# Ex_EEPROM_SOP16.net
KiCad netlist of a schematic drawn in EAGLE
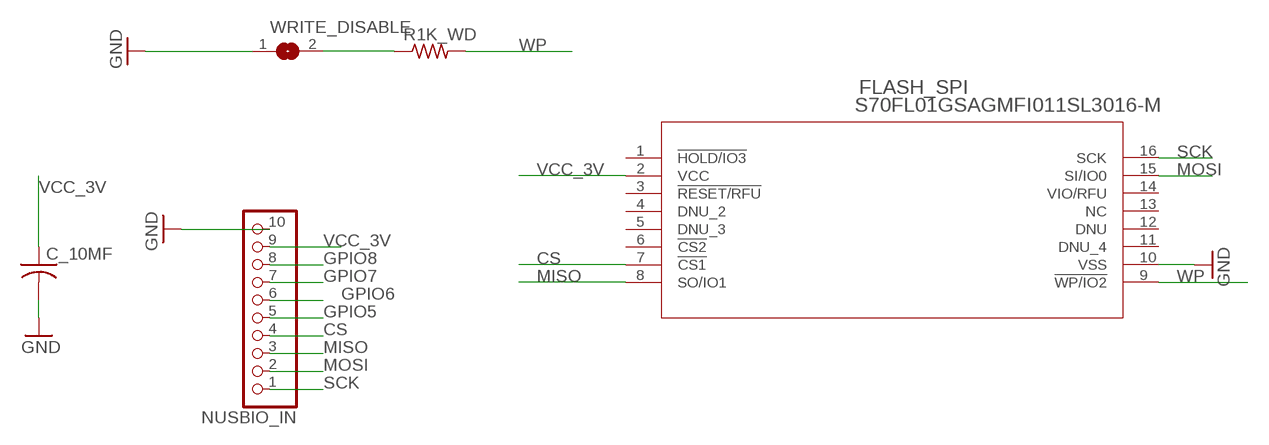
[diagram p0: schematic, sheet 1]

(export (version "E")
  (design (tool "Eeschema 10.0.6"))
  (components
    (comp (ref "C_10MF")
      (value "C-USC1206")
      (footprint "eagle-import:C1206")
      (libsource (lib "eagle-import") (part "C-USC1206"))
    )
    (comp (ref "FLASH_SPI")
      (value "S70FL01GSAGMFI011SL3016-M")
      (footprint "eagle-import:SL3016-M")
      (fields (field (name "MANUFACTURER_PART_NUMBER") "S70FL01GSAGMFI011"))
      (libsource (lib "eagle-import") (part "S70FL01GSAGMFI011SL3016-M"))
    )
    (comp (ref "NUSBIO_IN")
      (value "PINHD-1X10")
      (footprint "eagle-import:1X10-BIG")
      (libsource (lib "eagle-import") (part "PINHD-1X10"))
    )
    (comp (ref "R1K_WD")
      (value "R-US_R1206")
      (footprint "eagle-import:R1206")
      (libsource (lib "eagle-import") (part "R-US_R1206"))
    )
    (comp (ref "WRITE_DISABLE")
      (value "SOLDERJUMPERREFLOW")
      (footprint "eagle-import:SOLDERJUMPER_REFLOW")
      (libsource (lib "eagle-import") (part "SOLDERJUMPERREFLOW"))
    )
  )
  (nets
    (net (code "1") (name "/CS") (class "Default")
      (node (ref "FLASH_SPI") (pin "7") (pinfunction "~{CS1}_7") (pintype "input"))
      (node (ref "NUSBIO_IN") (pin "4") (pinfunction "4_4") (pintype "passive"))
    )
    (net (code "2") (name "/GPIO5") (class "Default")
      (node (ref "NUSBIO_IN") (pin "5") (pinfunction "5_5") (pintype "passive"))
    )
    (net (code "3") (name "/GPIO6") (class "Default")
      (node (ref "NUSBIO_IN") (pin "6") (pinfunction "6_6") (pintype "passive"))
    )
    (net (code "4") (name "/GPIO7") (class "Default")
      (node (ref "NUSBIO_IN") (pin "7") (pinfunction "7_7") (pintype "passive"))
    )
    (net (code "5") (name "/GPIO8") (class "Default")
      (node (ref "NUSBIO_IN") (pin "8") (pinfunction "8_8") (pintype "passive"))
    )
    (net (code "6") (name "/MISO") (class "Default")
      (node (ref "FLASH_SPI") (pin "8") (pinfunction "SO/IO1_8") (pintype "bidirectional"))
      (node (ref "NUSBIO_IN") (pin "3") (pinfunction "3_3") (pintype "passive"))
    )
    (net (code "7") (name "/MOSI") (class "Default")
      (node (ref "FLASH_SPI") (pin "15") (pinfunction "SI/IO0_15") (pintype "bidirectional"))
      (node (ref "NUSBIO_IN") (pin "2") (pinfunction "2_2") (pintype "passive"))
    )
    (net (code "8") (name "/SCK") (class "Default")
      (node (ref "FLASH_SPI") (pin "16") (pinfunction "SCK_16") (pintype "input"))
      (node (ref "NUSBIO_IN") (pin "1") (pinfunction "1_1") (pintype "passive"))
    )
    (net (code "9") (name "/VCC_3V") (class "Default")
      (node (ref "C_10MF") (pin "1") (pinfunction "1_1") (pintype "passive"))
      (node (ref "FLASH_SPI") (pin "2") (pinfunction "VCC_2") (pintype "power_in"))
      (node (ref "NUSBIO_IN") (pin "9") (pinfunction "9_9") (pintype "passive"))
    )
    (net (code "10") (name "/WP") (class "Default")
      (node (ref "FLASH_SPI") (pin "9") (pinfunction "~{WP/IO2}_9") (pintype "bidirectional"))
      (node (ref "R1K_WD") (pin "2") (pinfunction "2_2") (pintype "passive"))
    )
    (net (code "11") (name "GND") (class "Default")
      (node (ref "C_10MF") (pin "2") (pinfunction "2_2") (pintype "passive"))
      (node (ref "FLASH_SPI") (pin "10") (pinfunction "VSS_10") (pintype "power_in"))
      (node (ref "NUSBIO_IN") (pin "10") (pinfunction "10_10") (pintype "passive"))
      (node (ref "WRITE_DISABLE") (pin "1") (pinfunction "1_1") (pintype "passive"))
    )
    (net (code "12") (name "Net-(R1K_WD-Pad1)") (class "Default")
      (node (ref "R1K_WD") (pin "1") (pinfunction "1_1") (pintype "passive"))
      (node (ref "WRITE_DISABLE") (pin "2") (pinfunction "2_2") (pintype "passive"))
    )
    (net (code "13") (name "unconnected-(FLASH_SPI-DNU-Pad12)") (class "Default")
      (node (ref "FLASH_SPI") (pin "12") (pinfunction "DNU_12") (pintype "no_connect"))
    )
    (net (code "14") (name "unconnected-(FLASH_SPI-DNU_2-Pad4)") (class "Default")
      (node (ref "FLASH_SPI") (pin "4") (pinfunction "DNU_2_4") (pintype "no_connect"))
    )
    (net (code "15") (name "unconnected-(FLASH_SPI-DNU_3-Pad5)") (class "Default")
      (node (ref "FLASH_SPI") (pin "5") (pinfunction "DNU_3_5") (pintype "no_connect"))
    )
    (net (code "16") (name "unconnected-(FLASH_SPI-DNU_4-Pad11)") (class "Default")
      (node (ref "FLASH_SPI") (pin "11") (pinfunction "DNU_4_11") (pintype "no_connect"))
    )
    (net (code "17") (name "unconnected-(FLASH_SPI-NC-Pad13)") (class "Default")
      (node (ref "FLASH_SPI") (pin "13") (pinfunction "NC_13") (pintype "no_connect"))
    )
    (net (code "18") (name "unconnected-(FLASH_SPI-VIO{slash}RFU-Pad14)") (class "Default")
      (node (ref "FLASH_SPI") (pin "14") (pinfunction "VIO/RFU_14") (pintype "bidirectional"))
    )
    (net (code "19") (name "unconnected-(FLASH_SPI-~{CS2}-Pad6)") (class "Default")
      (node (ref "FLASH_SPI") (pin "6") (pinfunction "~{CS2}_6") (pintype "input"))
    )
    (net (code "20") (name "unconnected-(FLASH_SPI-~{HOLD{slash}IO3}-Pad1)") (class "Default")
      (node (ref "FLASH_SPI") (pin "1") (pinfunction "~{HOLD/IO3}_1") (pintype "bidirectional"))
    )
    (net (code "21") (name "unconnected-(FLASH_SPI-~{RESET{slash}RFU}-Pad3)") (class "Default")
      (node (ref "FLASH_SPI") (pin "3") (pinfunction "~{RESET/RFU}_3") (pintype "passive"))
    )
  )
)
